# Power_Distribution_Board.net
KiCad netlist of a schematic drawn in Altium Designer
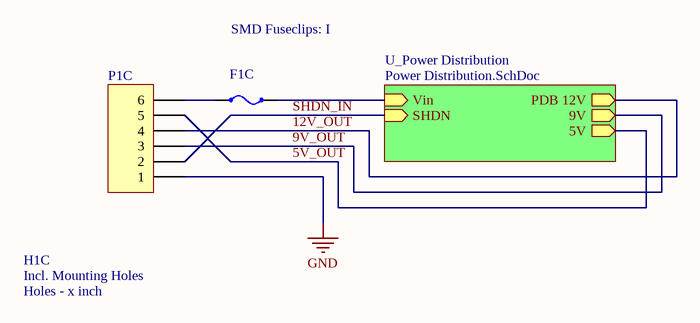
[diagram p0: Power Distribution Board.SchDoc]

(export (version "E")
  (design (tool "Eeschema 10.0.6"))
  (components
    (comp (ref "F1C")
      (value "3569TR")
      (footprint "Horizontal SMD fuse clip")
      (description "Fuse Clip Assembly")
      (libsource (lib "Keystone SchLib") (part "3569TR"))
    )
    (comp (ref "H1C")
      (value "Holes - x inch")
      (footprint "110mil Holes - 1.6 Inch")
      (libsource (lib "URC") (part "Holes - x inch"))
    )
    (comp (ref "i1C")
      (value "3569TR (Placeholder)")
      (description "Fuse Clip")
      (fields (field (name "MANUFACTURER PART NUMBER") "3569TR"))
      (libsource (lib "Keystone SchLib") (part "3569TR (Placeholder)"))
    )
    (comp (ref "P1C")
      (value "MSTBA 2,5/ 6-G-5,08")
      (footprint "MSTBA 2,5 6-G-5,08")
      (description "Header, 6-Pin")
      (fields (field (name "MANUFACTURER PART NUMBER") "1757284"))
      (libsource (lib "Pheonix Connectors") (part "MSTBA 2,5/ 6-G-5,08"))
    )
  )
  (nets
    (net (code "1") (name "/5V_OUT") (class "Default")
      (node (ref "P1C") (pin "5") (pinfunction "5_5") (pintype "passive"))
    )
    (net (code "2") (name "/9V_OUT") (class "Default")
      (node (ref "P1C") (pin "3") (pinfunction "3_3") (pintype "passive"))
    )
    (net (code "3") (name "/12V_OUT") (class "Default")
      (node (ref "P1C") (pin "4") (pinfunction "4_4") (pintype "passive"))
    )
    (net (code "4") (name "/SHDN_IN") (class "Default")
      (node (ref "P1C") (pin "2") (pinfunction "2_2") (pintype "passive"))
    )
    (net (code "5") (name "/Vin") (class "Default")
      (node (ref "F1C") (pin "2") (pinfunction "2_2") (pintype "passive"))
    )
    (net (code "6") (name "GND") (class "Default")
      (node (ref "P1C") (pin "1") (pinfunction "1_1") (pintype "passive"))
    )
    (net (code "7") (name "Net-(F1C-Pad1)") (class "Default")
      (node (ref "F1C") (pin "1") (pinfunction "1_1") (pintype "passive"))
      (node (ref "P1C") (pin "6") (pinfunction "6_6") (pintype "passive"))
    )
  )
)
